# Esquematico.net
KiCad netlist of a schematic drawn in Altium Designer
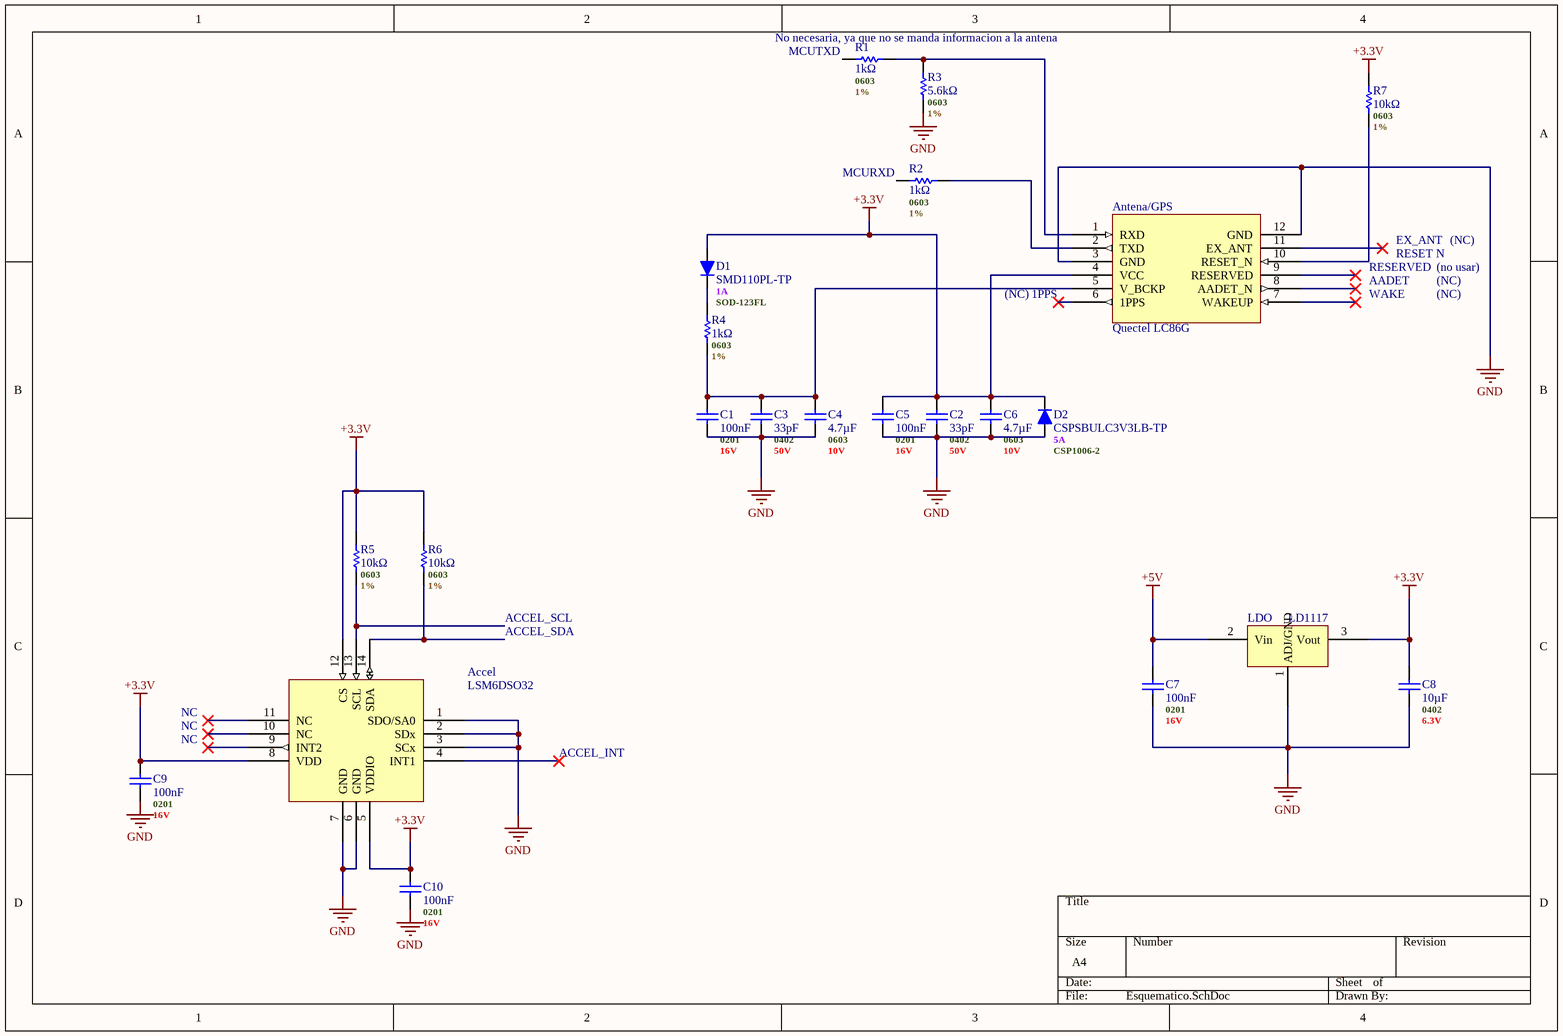
[diagram p0: Esquematico.SchDoc]

(export (version "E")
  (design (tool "Eeschema 10.0.6"))
  (components
    (comp (ref "Accel")
      (value "LSM6DSO32")
      (footprint "14-LGA - STMicroelectronics V4")
      (description "Accelerometer and 3D Gyroscope 3D Always-On 1.71V to 3.6V 0.55mA 14-Pin LGA T/R")
      (fields
        (field (name "MANUFACTURER") "STMicroelectronics")
        (field (name "MANUFACTURER PART NUMBER") "LSM6DSO32TR")
      )
      (libsource (lib "Accel") (part "LSM6DSO32"))
    )
    (comp (ref "Antena/GPS")
      (value "Quectel LC86G")
      (footprint "Quectel-LC86L")
      (description "GNSS Module, BeiDou, Galileo, GLONASS, GPS, QZSS, 1.605375GHz, -166 dBm, 25 s, 2.55V to 3.6V")
      (fields (field (name "MANUFACTURER") "Quectel") (field (name "MANUFACTURER PART NUMBER") "LC86GLAMD"))
      (libsource (lib "GPS") (part "Quectel LC86G"))
    )
    (comp (ref "C1")
      (value "100nF")
      (footprint "CAPC0603X33N")
      (description "0201 0.1 uF 16 V ±10% Tolerance X7S Multilayer Ceramic Chip Capacitor")
      (fields
        (field (name ".CASE/PACKAGE") "0201")
        (field (name ".VOLTAGE RATING (DC)") "16V")
        (field (name "MANUFACTURER") "Murata")
        (field (name "MANUFACTURER PART NUMBER") "GRM033C71C104KE14D")
      )
      (libsource (lib "CAP - GENERIC") (part "CAP - GENERIC"))
    )
    (comp (ref "C2")
      (value "33pF")
      (footprint "CAP_CL05_SAM")
      (fields
        (field (name ".CASE/PACKAGE") "0402")
        (field (name ".VOLTAGE RATING (DC)") "50V")
        (field (name "MANUFACTURER") "Samsung Electro-Mechanics")
        (field (name "MANUFACTURER PART NUMBER") "CL05C330JB5NNNC")
        (field (name "TOLERANCE") "5%")
      )
      (libsource (lib "CAP - GENERIC") (part "CAP - GENERIC"))
    )
    (comp (ref "C3")
      (value "33pF")
      (footprint "CAP_CL05_SAM")
      (fields
        (field (name ".CASE/PACKAGE") "0402")
        (field (name ".VOLTAGE RATING (DC)") "50V")
        (field (name "MANUFACTURER") "Samsung Electro-Mechanics")
        (field (name "MANUFACTURER PART NUMBER") "CL05C330JB5NNNC")
        (field (name "TOLERANCE") "5%")
      )
      (libsource (lib "CAP - GENERIC") (part "CAP - GENERIC"))
    )
    (comp (ref "C4")
      (value "4.7µF")
      (footprint "0603-capacitor4.7uf")
      (fields
        (field (name ".CASE/PACKAGE") "0603")
        (field (name ".VOLTAGE RATING (DC)") "10V")
        (field (name "MANUFACTURER") "Cal-Chip Electronics")
        (field (name "MANUFACTURER PART NUMBER") "GMC10X7R475K10NT")
      )
      (libsource (lib "CAP - GENERIC") (part "CAP - GENERIC"))
    )
    (comp (ref "C5")
      (value "100nF")
      (footprint "CAPC0603X33N")
      (description "0201 0.1 uF 16 V ±10% Tolerance X7S Multilayer Ceramic Chip Capacitor")
      (fields
        (field (name ".CASE/PACKAGE") "0201")
        (field (name ".VOLTAGE RATING (DC)") "16V")
        (field (name "MANUFACTURER") "Murata")
        (field (name "MANUFACTURER PART NUMBER") "GRM033C71C104KE14D")
      )
      (libsource (lib "CAP - GENERIC") (part "CAP - GENERIC"))
    )
    (comp (ref "C6")
      (value "4.7µF")
      (footprint "0603-capacitor4.7uf")
      (fields
        (field (name ".CASE/PACKAGE") "0603")
        (field (name ".VOLTAGE RATING (DC)") "10V")
        (field (name "MANUFACTURER") "Cal-Chip Electronics")
        (field (name "MANUFACTURER PART NUMBER") "GMC10X7R475K10NT")
      )
      (libsource (lib "CAP - GENERIC") (part "CAP - GENERIC"))
    )
    (comp (ref "C7")
      (value "100nF")
      (footprint "CAPC0603X33N")
      (description "0201 0.1 uF 16 V ±10% Tolerance X7S Multilayer Ceramic Chip Capacitor")
      (fields
        (field (name ".CASE/PACKAGE") "0201")
        (field (name ".VOLTAGE RATING (DC)") "16V")
        (field (name "MANUFACTURER") "Murata")
        (field (name "MANUFACTURER PART NUMBER") "GRM033C71C104KE14D")
      )
      (libsource (lib "CAP - GENERIC") (part "CAP - GENERIC"))
    )
    (comp (ref "C8")
      (value "10µF")
      (footprint "CAP_CL05_SAM")
      (description "6.3V 10uF X5R ±20% 0402 Multilayer Ceramic Capacitors MLCC - SMD/SMT ROHS")
      (fields
        (field (name ".CASE/PACKAGE") "0402")
        (field (name ".VOLTAGE RATING (DC)") "6.3V")
        (field (name "MANUFACTURER") "Samsung Electro-Mechanics")
        (field (name "MANUFACTURER PART NUMBER") "CL05A106MQ5NUNC")
      )
      (libsource (lib "CAP - GENERIC") (part "CAP - GENERIC"))
    )
    (comp (ref "C9")
      (value "100nF")
      (footprint "CAPC0603X33N")
      (description "0201 0.1 uF 16 V ±10% Tolerance X7S Multilayer Ceramic Chip Capacitor")
      (fields
        (field (name ".CASE/PACKAGE") "0201")
        (field (name ".VOLTAGE RATING (DC)") "16V")
        (field (name "MANUFACTURER") "Murata")
        (field (name "MANUFACTURER PART NUMBER") "GRM033C71C104KE14D")
      )
      (libsource (lib "CAP - GENERIC") (part "CAP - GENERIC"))
    )
    (comp (ref "C10")
      (value "100nF")
      (footprint "CAPC0603X33N")
      (description "0201 0.1 uF 16 V ±10% Tolerance X7S Multilayer Ceramic Chip Capacitor")
      (fields
        (field (name ".CASE/PACKAGE") "0201")
        (field (name ".VOLTAGE RATING (DC)") "16V")
        (field (name "MANUFACTURER") "Murata")
        (field (name "MANUFACTURER PART NUMBER") "GRM033C71C104KE14D")
      )
      (libsource (lib "CAP - GENERIC") (part "CAP - GENERIC"))
    )
    (comp (ref "D1")
      (value "SMD110PL-TP")
      (footprint "SOD-123FL_MCC")
      (description "Rectifier Diode, Schottky, 1 Phase, 1 Element, 1A, 100V V(RRM), Silicon")
      (fields
        (field (name ".CURRENT") "1A")
        (field (name ".CASE/PACKAGE") "SOD-123FL")
        (field (name "MANUFACTURER") "MCC")
      )
      (libsource (lib "DIODE - GENERIC") (part "DIODE"))
    )
    (comp (ref "D2")
      (value "CSPSBULC3V3LB-TP")
      (footprint "CSPSBULC3V3LBTP")
      (description "Trans Voltage Suppressor Diode, 13W, 3.3V V(RWM), Bidirectional, 1 Element, Silicon")
      (fields
        (field (name ".CURRENT") "5A")
        (field (name ".CASE/PACKAGE") "CSP1006-2")
        (field (name "MANUFACTURER") "MCC")
      )
      (libsource (lib "DIODE - GENERIC") (part "DIODE"))
    )
    (comp (ref "LDO")
      (value "LD1117")
      (footprint "DPAK-LD1117DT33TR V2")
      (description "Output ail-to- ail Very-Low-Noise Operational Amplifier 14-SOIC -40 to 125")
      (fields
        (field (name "MANUFACTURER") "STMicroelectronics")
        (field (name "MANUFACTURER PART NUMBER") "LD1117DT33TR")
      )
      (libsource (lib "LDO") (part "LD1117"))
    )
    (comp (ref "R1")
      (value "1kΩ")
      (footprint "RC0603N_YAG")
      (description "Fixed Resistor, Thin Film, 0.1W, 1000ohm, 75V, 1% +/-Tol, 50ppm/Cel, Surface Mount, 0603")
      (fields
        (field (name ".CASE/PACKAGE") "0603")
        (field (name ".TOLERANCE") "1%")
        (field (name "MANUFACTURER") "Yageo Group")
        (field (name "MANUFACTURER PART NUMBER") "RT0603FRE071KL")
      )
      (libsource (lib "RESISTOR - GENERIC") (part "RESISTOR - GENERIC"))
    )
    (comp (ref "R2")
      (value "1kΩ")
      (footprint "RC0603N_YAG")
      (description "Fixed Resistor, Thin Film, 0.1W, 1000ohm, 75V, 1% +/-Tol, 50ppm/Cel, Surface Mount, 0603")
      (fields
        (field (name ".CASE/PACKAGE") "0603")
        (field (name ".TOLERANCE") "1%")
        (field (name "MANUFACTURER") "Yageo Group")
        (field (name "MANUFACTURER PART NUMBER") "RT0603FRE071KL")
      )
      (libsource (lib "RESISTOR - GENERIC") (part "RESISTOR - GENERIC"))
    )
    (comp (ref "R3")
      (value "5.6kΩ")
      (footprint "RC0603N_YAG")
      (description "Res Thick Film 0603 5.6K Ohm 1% 0.1W(1/10W) ±100ppm/C Pad SMD T/R")
      (fields
        (field (name ".CASE/PACKAGE") "0603")
        (field (name ".TOLERANCE") "1%")
        (field (name "MANUFACTURER") "Yageo Group")
        (field (name "MANUFACTURER PART NUMBER") "RC0603FR-075K6L")
      )
      (libsource (lib "RESISTOR - GENERIC") (part "RESISTOR - GENERIC"))
    )
    (comp (ref "R4")
      (value "1kΩ")
      (footprint "RC0603N_YAG")
      (description "Fixed Resistor, Thin Film, 0.1W, 1000ohm, 75V, 1% +/-Tol, 50ppm/Cel, Surface Mount, 0603")
      (fields
        (field (name ".CASE/PACKAGE") "0603")
        (field (name ".TOLERANCE") "1%")
        (field (name "MANUFACTURER") "Yageo Group")
        (field (name "MANUFACTURER PART NUMBER") "RT0603FRE071KL")
      )
      (libsource (lib "RESISTOR - GENERIC") (part "RESISTOR - GENERIC"))
    )
    (comp (ref "R5")
      (value "10kΩ")
      (footprint "RC0603N_YAG")
      (description "100mW Thick Film Resistors 75V ±100ppm/℃ ±1% 10kΩ 0603 Chip Resistor - Surface Mount ROHS")
      (fields
        (field (name ".CASE/PACKAGE") "0603")
        (field (name ".TOLERANCE") "1%")
        (field (name "MANUFACTURER") "Yageo Group")
        (field (name "MANUFACTURER PART NUMBER") "RC0603FR-0710KL")
      )
      (libsource (lib "RESISTOR - GENERIC") (part "RESISTOR - GENERIC"))
    )
    (comp (ref "R6")
      (value "10kΩ")
      (footprint "RC0603N_YAG")
      (description "100mW Thick Film Resistors 75V ±100ppm/℃ ±1% 10kΩ 0603 Chip Resistor - Surface Mount ROHS")
      (fields
        (field (name ".CASE/PACKAGE") "0603")
        (field (name ".TOLERANCE") "1%")
        (field (name "MANUFACTURER") "Yageo Group")
        (field (name "MANUFACTURER PART NUMBER") "RC0603FR-0710KL")
      )
      (libsource (lib "RESISTOR - GENERIC") (part "RESISTOR - GENERIC"))
    )
    (comp (ref "R7")
      (value "10kΩ")
      (footprint "RC0603N_YAG")
      (description "100mW Thick Film Resistors 75V ±100ppm/℃ ±1% 10kΩ 0603 Chip Resistor - Surface Mount ROHS")
      (fields
        (field (name ".CASE/PACKAGE") "0603")
        (field (name ".TOLERANCE") "1%")
        (field (name "MANUFACTURER") "Yageo Group")
        (field (name "MANUFACTURER PART NUMBER") "RC0603FR-0710KL")
      )
      (libsource (lib "RESISTOR - GENERIC") (part "RESISTOR - GENERIC"))
    )
  )
  (nets
    (net (code "1") (name "+3.3V") (class "Default")
      (node (ref "Accel") (pin "12") (pinfunction "CS_12") (pintype "input"))
      (node (ref "Accel") (pin "5") (pinfunction "VDDIO_5") (pintype "power_in"))
      (node (ref "Accel") (pin "8") (pinfunction "VDD_8") (pintype "power_in"))
      (node (ref "Antena/GPS") (pin "4") (pinfunction "VCC_4") (pintype "power_in"))
      (node (ref "C10") (pin "2") (pinfunction "2_2") (pintype "passive"))
      (node (ref "C2") (pin "1") (pinfunction "1_1") (pintype "passive"))
      (node (ref "C5") (pin "2") (pinfunction "2_2") (pintype "passive"))
      (node (ref "C6") (pin "2") (pinfunction "2_2") (pintype "passive"))
      (node (ref "C8") (pin "2") (pinfunction "2_2") (pintype "passive"))
      (node (ref "C9") (pin "2") (pinfunction "2_2") (pintype "passive"))
      (node (ref "D1") (pin "A") (pinfunction "A_A") (pintype "passive"))
      (node (ref "D2") (pin "K") (pinfunction "K_K") (pintype "passive"))
      (node (ref "LDO") (pin "3") (pinfunction "Vout_3") (pintype "power_in"))
      (node (ref "R5") (pin "2") (pinfunction "2_2") (pintype "passive"))
      (node (ref "R6") (pin "2") (pinfunction "2_2") (pintype "passive"))
      (node (ref "R7") (pin "2") (pinfunction "2_2") (pintype "passive"))
    )
    (net (code "2") (name "+5V") (class "Default")
      (node (ref "C7") (pin "2") (pinfunction "2_2") (pintype "passive"))
      (node (ref "LDO") (pin "2") (pinfunction "Vin_2") (pintype "power_in"))
    )
    (net (code "3") (name "GND") (class "Default")
      (node (ref "Accel") (pin "1") (pinfunction "SDO/SA0_1") (pintype "passive"))
      (node (ref "Accel") (pin "2") (pinfunction "SDx_2") (pintype "passive"))
      (node (ref "Accel") (pin "3") (pinfunction "SCx_3") (pintype "passive"))
      (node (ref "Accel") (pin "6") (pinfunction "GND_6") (pintype "power_in"))
      (node (ref "Accel") (pin "7") (pinfunction "GND_7") (pintype "power_in"))
      (node (ref "Antena/GPS") (pin "12") (pinfunction "GND_12") (pintype "power_in"))
      (node (ref "Antena/GPS") (pin "3") (pinfunction "GND_3") (pintype "power_in"))
      (node (ref "C1") (pin "1") (pinfunction "1_1") (pintype "passive"))
      (node (ref "C10") (pin "1") (pinfunction "1_1") (pintype "passive"))
      (node (ref "C2") (pin "2") (pinfunction "2_2") (pintype "passive"))
      (node (ref "C3") (pin "2") (pinfunction "2_2") (pintype "passive"))
      (node (ref "C4") (pin "1") (pinfunction "1_1") (pintype "passive"))
      (node (ref "C5") (pin "1") (pinfunction "1_1") (pintype "passive"))
      (node (ref "C6") (pin "1") (pinfunction "1_1") (pintype "passive"))
      (node (ref "C7") (pin "1") (pinfunction "1_1") (pintype "passive"))
      (node (ref "C8") (pin "1") (pinfunction "1_1") (pintype "passive"))
      (node (ref "C9") (pin "1") (pinfunction "1_1") (pintype "passive"))
      (node (ref "D2") (pin "A") (pinfunction "A_A") (pintype "passive"))
      (node (ref "LDO") (pin "1") (pinfunction "ADJ/GND_1") (pintype "power_in"))
      (node (ref "R3") (pin "1") (pinfunction "1_1") (pintype "passive"))
    )
    (net (code "4") (name "Net-(Accel-SCL)") (class "Default")
      (node (ref "Accel") (pin "13") (pinfunction "SCL_13") (pintype "input"))
      (node (ref "R5") (pin "1") (pinfunction "1_1") (pintype "passive"))
    )
    (net (code "5") (name "Net-(Accel-SDA)") (class "Default")
      (node (ref "Accel") (pin "14") (pinfunction "SDA_14") (pintype "bidirectional"))
      (node (ref "R6") (pin "1") (pinfunction "1_1") (pintype "passive"))
    )
    (net (code "6") (name "Net-(Antena/GPS-RESET_N)") (class "Default")
      (node (ref "Antena/GPS") (pin "10") (pinfunction "RESET_N_10") (pintype "input"))
      (node (ref "R7") (pin "1") (pinfunction "1_1") (pintype "passive"))
    )
    (net (code "7") (name "Net-(Antena/GPS-RXD)") (class "Default")
      (node (ref "Antena/GPS") (pin "1") (pinfunction "RXD_1") (pintype "input"))
      (node (ref "R1") (pin "2") (pinfunction "2_2") (pintype "passive"))
      (node (ref "R3") (pin "2") (pinfunction "2_2") (pintype "passive"))
    )
    (net (code "8") (name "Net-(Antena/GPS-TXD)") (class "Default")
      (node (ref "Antena/GPS") (pin "2") (pinfunction "TXD_2") (pintype "output"))
      (node (ref "R2") (pin "2") (pinfunction "2_2") (pintype "passive"))
    )
    (net (code "9") (name "Net-(Antena/GPS-V_BCKP)") (class "Default")
      (node (ref "Antena/GPS") (pin "5") (pinfunction "V_BCKP_5") (pintype "power_in"))
      (node (ref "C1") (pin "2") (pinfunction "2_2") (pintype "passive"))
      (node (ref "C3") (pin "1") (pinfunction "1_1") (pintype "passive"))
      (node (ref "C4") (pin "2") (pinfunction "2_2") (pintype "passive"))
      (node (ref "R4") (pin "1") (pinfunction "1_1") (pintype "passive"))
    )
    (net (code "10") (name "Net-(D1-PadK)") (class "Default")
      (node (ref "D1") (pin "K") (pinfunction "K_K") (pintype "passive"))
      (node (ref "R4") (pin "2") (pinfunction "2_2") (pintype "passive"))
    )
    (net (code "11") (name "unconnected-(Accel-INT1-Pad4)") (class "Default")
      (node (ref "Accel") (pin "4") (pinfunction "INT1_4") (pintype "passive+no_connect"))
    )
    (net (code "12") (name "unconnected-(Accel-INT2-Pad9)") (class "Default")
      (node (ref "Accel") (pin "9") (pinfunction "INT2_9") (pintype "output+no_connect"))
    )
    (net (code "13") (name "unconnected-(Accel-NC-Pad10)") (class "Default")
      (node (ref "Accel") (pin "10") (pinfunction "NC_10") (pintype "passive+no_connect"))
    )
    (net (code "14") (name "unconnected-(Accel-NC-Pad11)") (class "Default")
      (node (ref "Accel") (pin "11") (pinfunction "NC_11") (pintype "passive+no_connect"))
    )
    (net (code "15") (name "unconnected-(Antena/GPS-1PPS-Pad6)") (class "Default")
      (node (ref "Antena/GPS") (pin "6") (pinfunction "1PPS_6") (pintype "output+no_connect"))
    )
    (net (code "16") (name "unconnected-(Antena/GPS-AADET_N-Pad8)") (class "Default")
      (node (ref "Antena/GPS") (pin "8") (pinfunction "AADET_N_8") (pintype "output+no_connect"))
    )
    (net (code "17") (name "unconnected-(Antena/GPS-EX_ANT-Pad11)") (class "Default")
      (node (ref "Antena/GPS") (pin "11") (pinfunction "EX_ANT_11") (pintype "passive+no_connect"))
    )
    (net (code "18") (name "unconnected-(Antena/GPS-RESERVED-Pad9)") (class "Default")
      (node (ref "Antena/GPS") (pin "9") (pinfunction "RESERVED_9") (pintype "passive+no_connect"))
    )
    (net (code "19") (name "unconnected-(Antena/GPS-WAKEUP-Pad7)") (class "Default")
      (node (ref "Antena/GPS") (pin "7") (pinfunction "WAKEUP_7") (pintype "input+no_connect"))
    )
    (net (code "20") (name "unconnected-(R1-Pad1)") (class "Default")
      (node (ref "R1") (pin "1") (pinfunction "1_1") (pintype "passive"))
    )
    (net (code "21") (name "unconnected-(R2-Pad1)") (class "Default")
      (node (ref "R2") (pin "1") (pinfunction "1_1") (pintype "passive"))
    )
  )
)
